# Main.net
KiCad netlist of a schematic drawn in Altium Designer
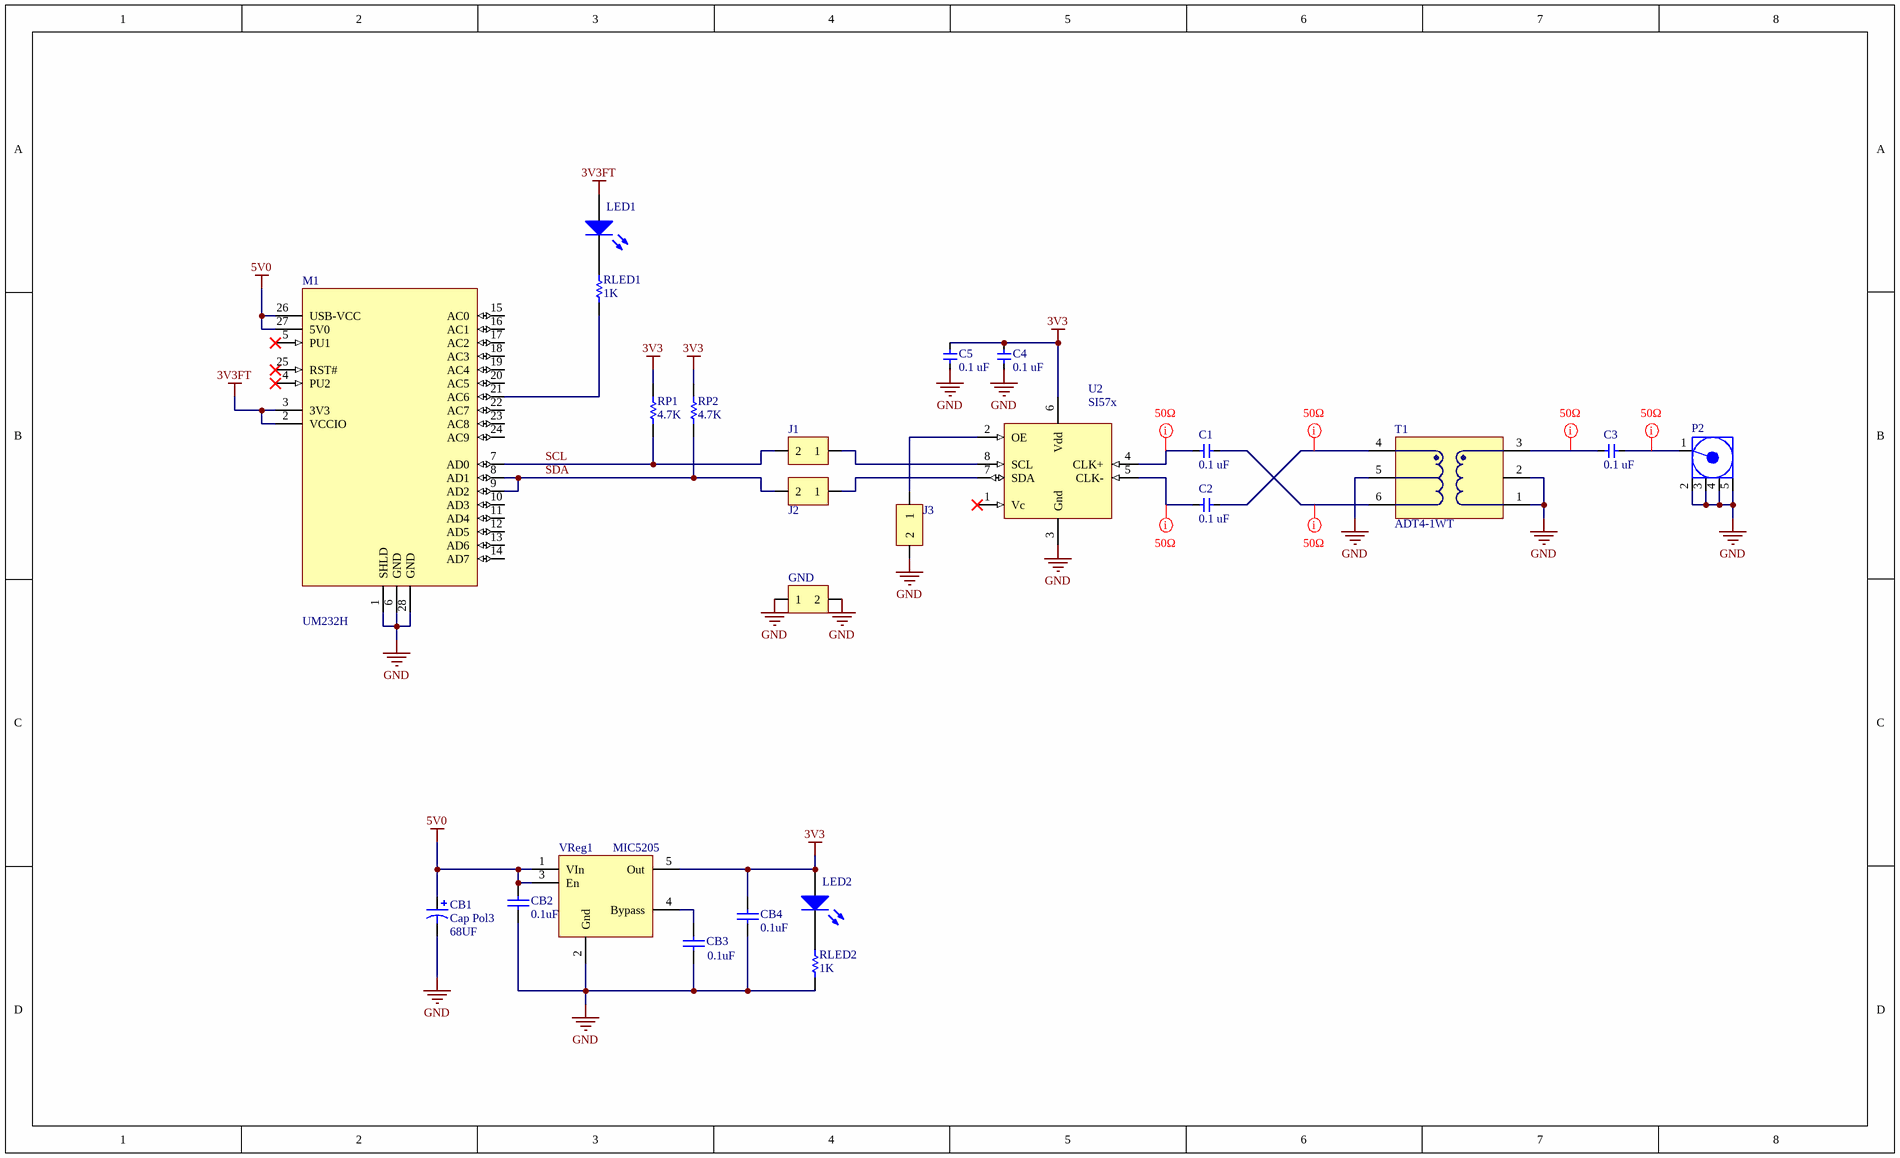
[diagram p0: Main.SchDoc]

(export (version "E")
  (design (tool "Eeschema 10.0.6"))
  (components
    (comp (ref "C1")
      (value "0.1 uF")
      (footprint "0603C")
      (description "SMT Cap")
      (fields (field (name "PUBLISHER") "Altium Limited"))
      (libsource (lib "Miscellaneous Devices") (part "Cap - SMT Small"))
    )
    (comp (ref "C2")
      (value "0.1 uF")
      (footprint "0603C")
      (description "SMT Cap")
      (fields (field (name "PUBLISHER") "Altium Limited"))
      (libsource (lib "Miscellaneous Devices") (part "Cap - SMT Small"))
    )
    (comp (ref "C3")
      (value "0.1 uF")
      (footprint "0603C")
      (description "SMT Cap")
      (fields (field (name "PUBLISHER") "Altium Limited"))
      (libsource (lib "Miscellaneous Devices") (part "Cap - SMT Small"))
    )
    (comp (ref "C4")
      (value "0.1 uF")
      (footprint "0603C")
      (description "SMT Cap")
      (fields (field (name "PUBLISHER") "Altium Limited"))
      (libsource (lib "Miscellaneous Devices") (part "Cap - SMT Small"))
    )
    (comp (ref "C5")
      (value "0.1 uF")
      (footprint "0603C")
      (description "SMT Cap")
      (fields (field (name "PUBLISHER") "Altium Limited"))
      (libsource (lib "Miscellaneous Devices") (part "Cap - SMT Small"))
    )
    (comp (ref "CB1")
      (value "Cap Pol3")
      (footprint "V")
      (description "KEMET T520 KO-CAP  Polymer SMT Tantalum")
      (fields (field (name "ALTIUM_VALUE") "68UF") (field (name "VOLTAGE") "10V"))
      (libsource (lib "Miscellaneous Devices") (part "Cap Pol3"))
    )
    (comp (ref "CB2")
      (value "0.1uF")
      (footprint "0603C")
      (description "Capacitor (Semiconductor SIM Model)")
      (fields (field (name "Comment") "Cap Semi") (field (name "PUBLISHER") "Altium Limited"))
      (libsource (lib "Miscellaneous Devices") (part "Cap Semi"))
    )
    (comp (ref "CB3")
      (value "0.1uF")
      (footprint "0603C")
      (description "Capacitor (Semiconductor SIM Model)")
      (fields (field (name "Comment") "Cap Semi") (field (name "PUBLISHER") "Altium Limited"))
      (libsource (lib "Miscellaneous Devices") (part "Cap Semi"))
    )
    (comp (ref "CB4")
      (value "0.1uF")
      (footprint "0603C")
      (description "Capacitor (Semiconductor SIM Model)")
      (fields (field (name "Comment") "Cap Semi") (field (name "PUBLISHER") "Altium Limited"))
      (libsource (lib "Miscellaneous Devices") (part "Cap Semi"))
    )
    (comp (ref "GND")
      (value "Jumper")
      (footprint "HDR1X2")
      (description "Jumper - 2-Pin")
      (fields (field (name "PUBLISHER") "Altium Limited"))
      (libsource (lib "") (part "Jumper - 2 Pin_1"))
    )
    (comp (ref "J1")
      (value "Jumper")
      (footprint "HDR1X2")
      (description "Jumper - 2-Pin")
      (fields (field (name "PUBLISHER") "Altium Limited"))
      (libsource (lib "Miscellaneous Connectors") (part "Jumper - 2 Pin"))
    )
    (comp (ref "J2")
      (value "Jumper")
      (footprint "HDR1X2")
      (description "Jumper - 2-Pin")
      (fields (field (name "PUBLISHER") "Altium Limited"))
      (libsource (lib "Miscellaneous Connectors") (part "Jumper - 2 Pin"))
    )
    (comp (ref "J3")
      (value "Jumper")
      (footprint "HDR1X2")
      (description "Jumper - 2-Pin")
      (fields (field (name "PUBLISHER") "Altium Limited"))
      (libsource (lib "") (part "Jumper - 2 Pin_2"))
    )
    (comp (ref "LED1")
      (value "LED2")
      (footprint "Chip LED 3220")
      (description "Typical RED, GREEN, YELLOW, AMBER GaAs LED")
      (fields (field (name "PUBLISHER") "Altium Limited"))
      (libsource (lib "Miscellaneous Devices") (part "LED2"))
    )
    (comp (ref "LED2")
      (value "LED2")
      (footprint "Chip LED 3220")
      (description "Typical RED, GREEN, YELLOW, AMBER GaAs LED")
      (fields (field (name "PUBLISHER") "Altium Limited"))
      (libsource (lib "Miscellaneous Devices") (part "LED2"))
    )
    (comp (ref "M1")
      (value "UM232H")
      (footprint "UM232H Module")
      (description "FTDI FT232H Dev Module")
      (libsource (lib "ICs") (part "UM232H"))
    )
    (comp (ref "P2")
      (value "COAX-M")
      (footprint "SMA Jack - PCB Edge - MultiSize")
      (description "RF Coaxial PCB Connector, MMCX; Thru-Hole, Vertical Mount Plug,  50 Ohm Impedance")
      (fields (field (name "PUBLISHER") "Altium Limited"))
      (libsource (lib "Miscellaneous Connectors") (part "COAX-M"))
    )
    (comp (ref "RLED1")
      (value "1K")
      (footprint "1206R")
      (description "Semiconductor Resistor")
      (fields (field (name "Comment") "Res Semi") (field (name "PUBLISHER") "Altium Limited"))
      (libsource (lib "Miscellaneous Devices") (part "Res Semi"))
    )
    (comp (ref "RLED2")
      (value "1K")
      (footprint "1206R")
      (description "Semiconductor Resistor")
      (fields (field (name "Comment") "Res Semi") (field (name "PUBLISHER") "Altium Limited"))
      (libsource (lib "Miscellaneous Devices") (part "Res Semi"))
    )
    (comp (ref "RP1")
      (value "4.7K")
      (footprint "1206R")
      (description "Semiconductor Resistor")
      (fields (field (name "Comment") "Res Semi") (field (name "PUBLISHER") "Altium Limited"))
      (libsource (lib "Miscellaneous Devices") (part "Res Semi"))
    )
    (comp (ref "RP2")
      (value "4.7K")
      (footprint "1206R")
      (description "Semiconductor Resistor")
      (fields (field (name "Comment") "Res Semi") (field (name "PUBLISHER") "Altium Limited"))
      (libsource (lib "Miscellaneous Devices") (part "Res Semi"))
    )
    (comp (ref "T1")
      (value "ADT4-1WT")
      (footprint "CD542")
      (description "Surface Mount RF Transformer")
      (libsource (lib "RF Components") (part "ADT4-1WT"))
    )
    (comp (ref "U2")
      (value "SI57x")
      (footprint "SI57x")
      (description "10 MHZ TO 1.4 GHZ I2C PROGRAMMABLE XO/VCXO")
      (libsource (lib "RF Components") (part "SI570"))
    )
    (comp (ref "VReg1")
      (value "MIC5205")
      (footprint "SOT23-5AN")
      (description "150mA Low-Noise LDO Regulator")
      (libsource (lib "DAQ System") (part "MIC5205"))
    )
  )
  (nets
    (net (code "1") (name "/SCL") (class "Default")
      (node (ref "J1") (pin "2") (pinfunction "2_2") (pintype "passive"))
      (node (ref "M1") (pin "7") (pinfunction "AD0_7") (pintype "bidirectional"))
      (node (ref "RP1") (pin "1") (pinfunction "1_1") (pintype "passive"))
    )
    (net (code "2") (name "/SDA") (class "Default")
      (node (ref "J2") (pin "2") (pinfunction "2_2") (pintype "passive"))
      (node (ref "M1") (pin "8") (pinfunction "AD1_8") (pintype "bidirectional"))
      (node (ref "M1") (pin "9") (pinfunction "AD2_9") (pintype "bidirectional"))
      (node (ref "RP2") (pin "1") (pinfunction "1_1") (pintype "passive"))
    )
    (net (code "3") (name "3V3") (class "Default")
      (node (ref "C4") (pin "2") (pinfunction "2_2") (pintype "passive"))
      (node (ref "C5") (pin "2") (pinfunction "2_2") (pintype "passive"))
      (node (ref "CB4") (pin "2") (pinfunction "2_2") (pintype "passive"))
      (node (ref "LED2") (pin "1") (pinfunction "A_1") (pintype "passive"))
      (node (ref "RP1") (pin "2") (pinfunction "2_2") (pintype "passive"))
      (node (ref "RP2") (pin "2") (pinfunction "2_2") (pintype "passive"))
      (node (ref "U2") (pin "6") (pinfunction "Vdd_6") (pintype "power_in"))
      (node (ref "VReg1") (pin "5") (pinfunction "Out_5") (pintype "power_in"))
    )
    (net (code "4") (name "3V3FT") (class "Default")
      (node (ref "LED1") (pin "1") (pinfunction "A_1") (pintype "passive"))
      (node (ref "M1") (pin "2") (pinfunction "VCCIO_2") (pintype "power_in"))
      (node (ref "M1") (pin "3") (pinfunction "3V3_3") (pintype "power_in"))
    )
    (net (code "5") (name "5V0") (class "Default")
      (node (ref "CB1") (pin "1") (pinfunction "1_1") (pintype "passive"))
      (node (ref "CB2") (pin "2") (pinfunction "2_2") (pintype "passive"))
      (node (ref "M1") (pin "26") (pinfunction "USB-VCC_26") (pintype "power_in"))
      (node (ref "M1") (pin "27") (pinfunction "5V0_27") (pintype "power_in"))
      (node (ref "VReg1") (pin "1") (pinfunction "VIn_1") (pintype "power_in"))
      (node (ref "VReg1") (pin "3") (pinfunction "En_3") (pintype "power_in"))
    )
    (net (code "6") (name "GND") (class "Default")
      (node (ref "C4") (pin "1") (pinfunction "1_1") (pintype "passive"))
      (node (ref "C5") (pin "1") (pinfunction "1_1") (pintype "passive"))
      (node (ref "CB1") (pin "2") (pinfunction "2_2") (pintype "passive"))
      (node (ref "CB2") (pin "1") (pinfunction "1_1") (pintype "passive"))
      (node (ref "CB3") (pin "1") (pinfunction "1_1") (pintype "passive"))
      (node (ref "CB4") (pin "1") (pinfunction "1_1") (pintype "passive"))
      (node (ref "GND") (pin "1") (pinfunction "1_1") (pintype "passive"))
      (node (ref "GND") (pin "2") (pinfunction "2_2") (pintype "passive"))
      (node (ref "J3") (pin "2") (pinfunction "2_2") (pintype "passive"))
      (node (ref "M1") (pin "1") (pinfunction "SHLD_1") (pintype "power_in"))
      (node (ref "M1") (pin "28") (pinfunction "GND_28") (pintype "power_in"))
      (node (ref "M1") (pin "6") (pinfunction "GND_6") (pintype "power_in"))
      (node (ref "P2") (pin "2") (pinfunction "GND_2") (pintype "power_in"))
      (node (ref "P2") (pin "3") (pinfunction "GND_3") (pintype "power_in"))
      (node (ref "P2") (pin "4") (pinfunction "GND_4") (pintype "power_in"))
      (node (ref "P2") (pin "5") (pinfunction "GND_5") (pintype "power_in"))
      (node (ref "RLED2") (pin "1") (pinfunction "1_1") (pintype "passive"))
      (node (ref "T1") (pin "1") (pinfunction "Input_1") (pintype "passive"))
      (node (ref "T1") (pin "2") (pinfunction "Gnd_2") (pintype "power_in"))
      (node (ref "T1") (pin "5") (pinfunction "Termination_5") (pintype "passive"))
      (node (ref "U2") (pin "3") (pinfunction "Gnd_3") (pintype "power_in"))
      (node (ref "VReg1") (pin "2") (pinfunction "Gnd_2") (pintype "power_in"))
    )
    (net (code "7") (name "Net-(C2-Pad2)") (class "Default")
      (node (ref "C2") (pin "2") (pinfunction "2_2") (pintype "passive"))
      (node (ref "T1") (pin "4") (pinfunction "Termination_4") (pintype "passive"))
    )
    (net (code "8") (name "Net-(LED1-K)") (class "Default")
      (node (ref "LED1") (pin "2") (pinfunction "K_2") (pintype "passive"))
      (node (ref "RLED1") (pin "2") (pinfunction "2_2") (pintype "passive"))
    )
    (net (code "9") (name "Net-(LED2-K)") (class "Default")
      (node (ref "LED2") (pin "2") (pinfunction "K_2") (pintype "passive"))
      (node (ref "RLED2") (pin "2") (pinfunction "2_2") (pintype "passive"))
    )
    (net (code "10") (name "Net-(M1-AC6)") (class "Default")
      (node (ref "M1") (pin "21") (pinfunction "AC6_21") (pintype "bidirectional"))
      (node (ref "RLED1") (pin "1") (pinfunction "1_1") (pintype "passive"))
    )
    (net (code "11") (name "Net-(P2-Signal)") (class "Default")
      (node (ref "C3") (pin "2") (pinfunction "2_2") (pintype "passive"))
      (node (ref "P2") (pin "1") (pinfunction "Signal_1") (pintype "passive"))
    )
    (net (code "12") (name "Net-(T1-Coupled)") (class "Default")
      (node (ref "C3") (pin "1") (pinfunction "1_1") (pintype "passive"))
      (node (ref "T1") (pin "3") (pinfunction "Coupled_3") (pintype "passive"))
    )
    (net (code "13") (name "Net-(T1-Output)") (class "Default")
      (node (ref "C1") (pin "2") (pinfunction "2_2") (pintype "passive"))
      (node (ref "T1") (pin "6") (pinfunction "Output_6") (pintype "passive"))
    )
    (net (code "14") (name "Net-(U2-CLK+)") (class "Default")
      (node (ref "C1") (pin "1") (pinfunction "1_1") (pintype "passive"))
      (node (ref "U2") (pin "4") (pinfunction "CLK+_4") (pintype "input"))
    )
    (net (code "15") (name "Net-(U2-CLK-)") (class "Default")
      (node (ref "C2") (pin "1") (pinfunction "1_1") (pintype "passive"))
      (node (ref "U2") (pin "5") (pinfunction "CLK-_5") (pintype "input"))
    )
    (net (code "16") (name "Net-(U2-OE)") (class "Default")
      (node (ref "J3") (pin "1") (pinfunction "1_1") (pintype "passive"))
      (node (ref "U2") (pin "2") (pinfunction "OE_2") (pintype "input"))
    )
    (net (code "17") (name "Net-(U2-SCL)") (class "Default")
      (node (ref "J1") (pin "1") (pinfunction "1_1") (pintype "passive"))
      (node (ref "U2") (pin "8") (pinfunction "SCL_8") (pintype "input"))
    )
    (net (code "18") (name "Net-(U2-SDA)") (class "Default")
      (node (ref "J2") (pin "1") (pinfunction "1_1") (pintype "passive"))
      (node (ref "U2") (pin "7") (pinfunction "SDA_7") (pintype "bidirectional"))
    )
    (net (code "19") (name "Net-(VReg1-Bypass)") (class "Default")
      (node (ref "CB3") (pin "2") (pinfunction "2_2") (pintype "passive"))
      (node (ref "VReg1") (pin "4") (pinfunction "Bypass_4") (pintype "power_in"))
    )
    (net (code "20") (name "unconnected-(M1-AC0-Pad15)") (class "Default")
      (node (ref "M1") (pin "15") (pinfunction "AC0_15") (pintype "bidirectional"))
    )
    (net (code "21") (name "unconnected-(M1-AC1-Pad16)") (class "Default")
      (node (ref "M1") (pin "16") (pinfunction "AC1_16") (pintype "bidirectional"))
    )
    (net (code "22") (name "unconnected-(M1-AC2-Pad17)") (class "Default")
      (node (ref "M1") (pin "17") (pinfunction "AC2_17") (pintype "bidirectional"))
    )
    (net (code "23") (name "unconnected-(M1-AC3-Pad18)") (class "Default")
      (node (ref "M1") (pin "18") (pinfunction "AC3_18") (pintype "bidirectional"))
    )
    (net (code "24") (name "unconnected-(M1-AC4-Pad19)") (class "Default")
      (node (ref "M1") (pin "19") (pinfunction "AC4_19") (pintype "bidirectional"))
    )
    (net (code "25") (name "unconnected-(M1-AC5-Pad20)") (class "Default")
      (node (ref "M1") (pin "20") (pinfunction "AC5_20") (pintype "bidirectional"))
    )
    (net (code "26") (name "unconnected-(M1-AC7-Pad22)") (class "Default")
      (node (ref "M1") (pin "22") (pinfunction "AC7_22") (pintype "bidirectional"))
    )
    (net (code "27") (name "unconnected-(M1-AC8-Pad23)") (class "Default")
      (node (ref "M1") (pin "23") (pinfunction "AC8_23") (pintype "bidirectional"))
    )
    (net (code "28") (name "unconnected-(M1-AC9-Pad24)") (class "Default")
      (node (ref "M1") (pin "24") (pinfunction "AC9_24") (pintype "bidirectional"))
    )
    (net (code "29") (name "unconnected-(M1-AD3-Pad10)") (class "Default")
      (node (ref "M1") (pin "10") (pinfunction "AD3_10") (pintype "bidirectional"))
    )
    (net (code "30") (name "unconnected-(M1-AD4-Pad11)") (class "Default")
      (node (ref "M1") (pin "11") (pinfunction "AD4_11") (pintype "bidirectional"))
    )
    (net (code "31") (name "unconnected-(M1-AD5-Pad12)") (class "Default")
      (node (ref "M1") (pin "12") (pinfunction "AD5_12") (pintype "bidirectional"))
    )
    (net (code "32") (name "unconnected-(M1-AD6-Pad13)") (class "Default")
      (node (ref "M1") (pin "13") (pinfunction "AD6_13") (pintype "bidirectional"))
    )
    (net (code "33") (name "unconnected-(M1-AD7-Pad14)") (class "Default")
      (node (ref "M1") (pin "14") (pinfunction "AD7_14") (pintype "bidirectional"))
    )
    (net (code "34") (name "unconnected-(M1-PU1-Pad5)") (class "Default")
      (node (ref "M1") (pin "5") (pinfunction "PU1_5") (pintype "input+no_connect"))
    )
    (net (code "35") (name "unconnected-(M1-PU2-Pad4)") (class "Default")
      (node (ref "M1") (pin "4") (pinfunction "PU2_4") (pintype "input+no_connect"))
    )
    (net (code "36") (name "unconnected-(M1-RST#-Pad25)") (class "Default")
      (node (ref "M1") (pin "25") (pinfunction "RST#_25") (pintype "input+no_connect"))
    )
    (net (code "37") (name "unconnected-(U2-Vc-Pad1)") (class "Default")
      (node (ref "U2") (pin "1") (pinfunction "Vc_1") (pintype "input+no_connect"))
    )
  )
)
